# servo_controller.net
KiCad netlist of a schematic drawn in EAGLE
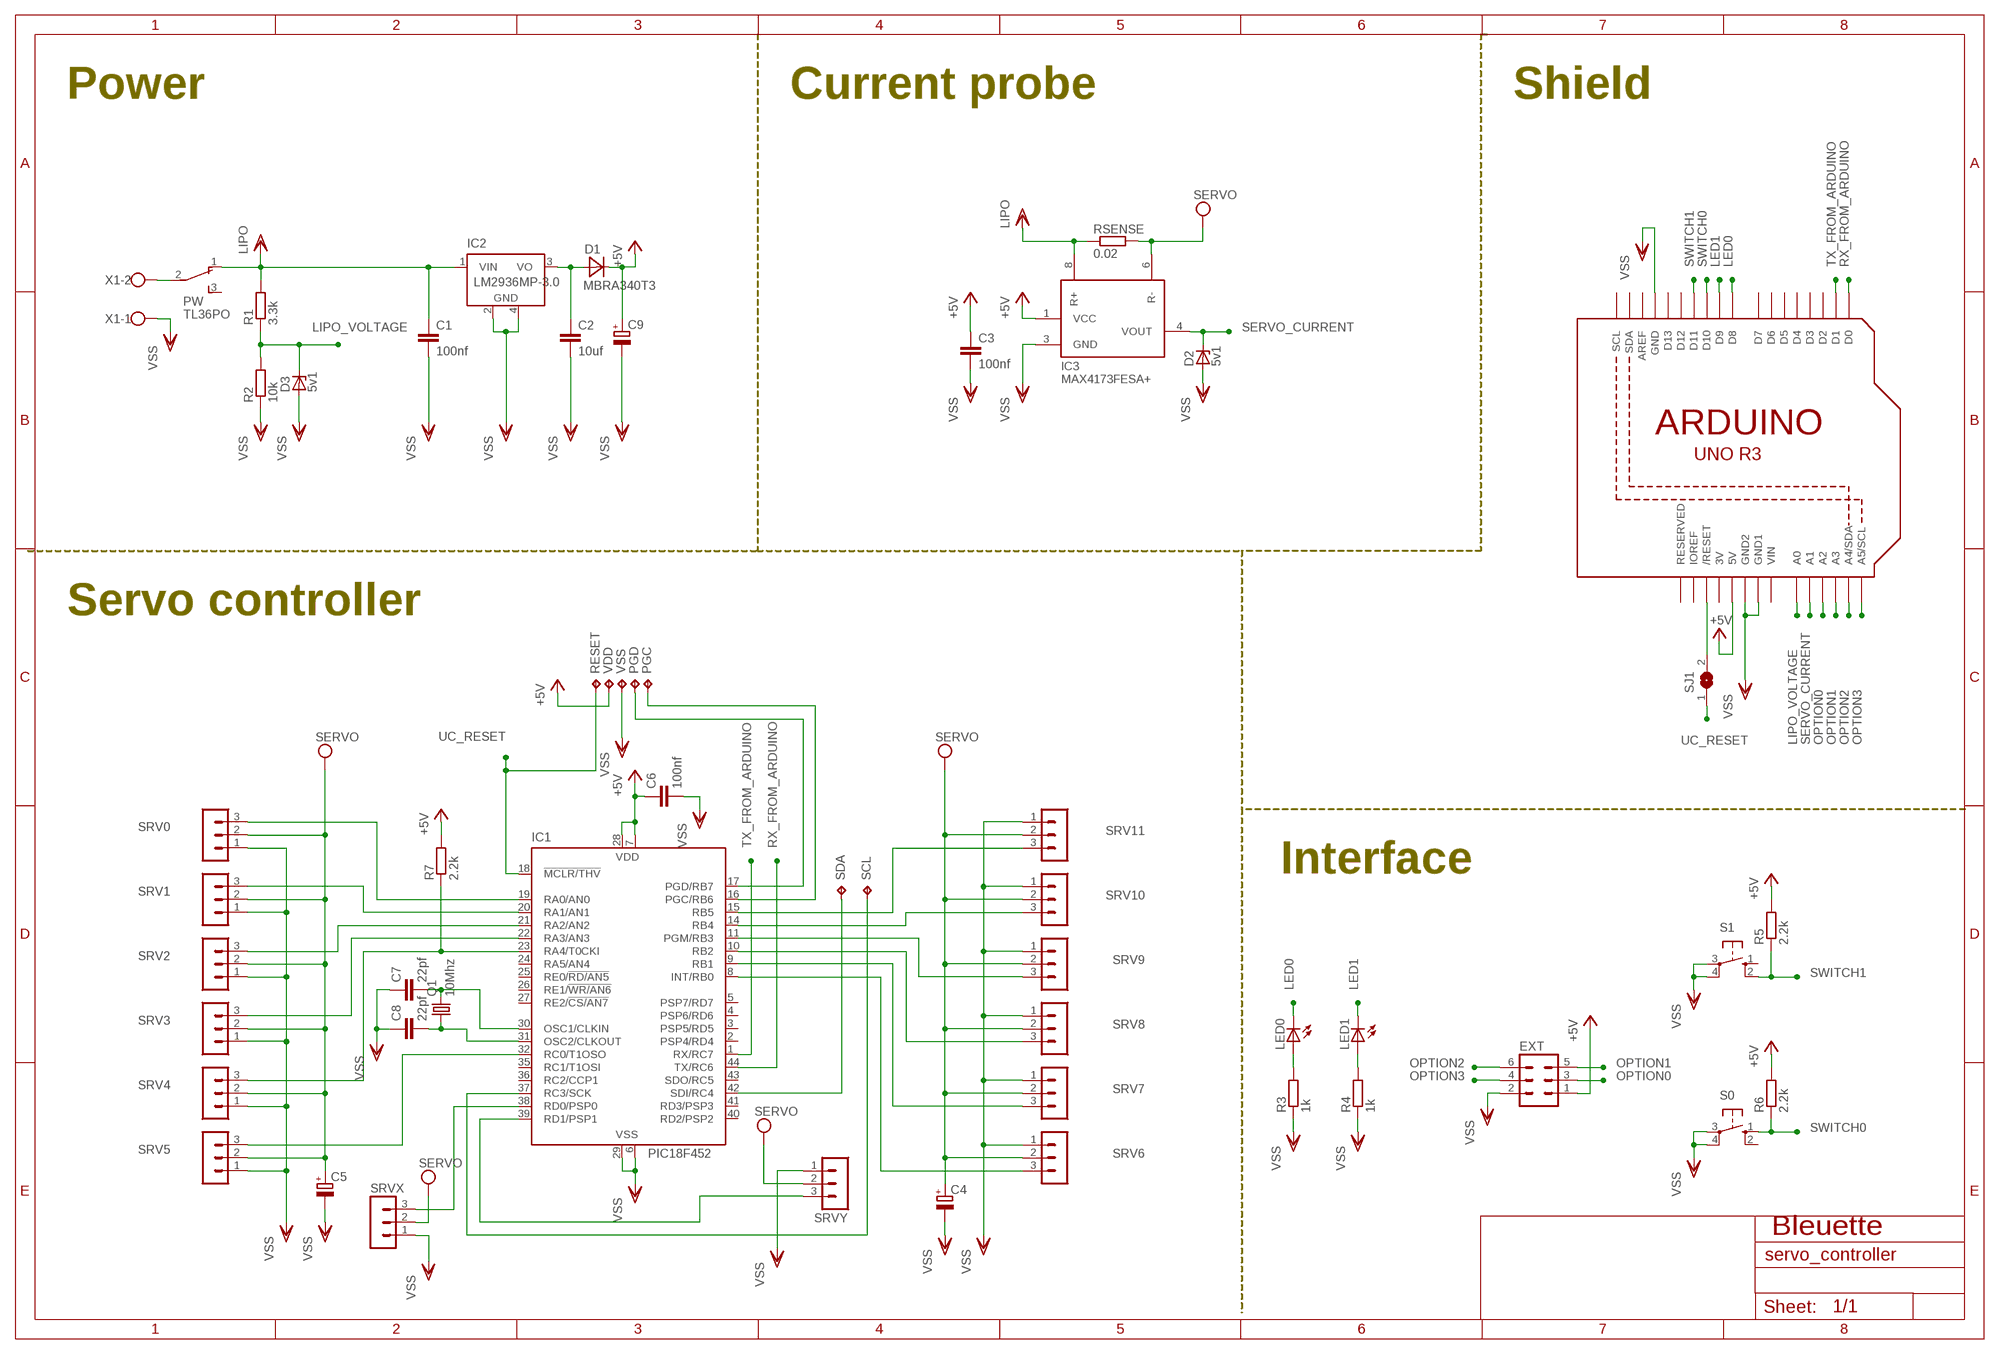
[diagram p0: schematic, sheet 1]

(export (version "E")
  (design (tool "Eeschema 10.0.6"))
  (components
    (comp (ref "C1")
      (value "100nf")
      (footprint "eagle-import:C1206")
      (libsource (lib "eagle-import") (part "C-EUC1206"))
    )
    (comp (ref "C2")
      (value "10uf")
      (footprint "eagle-import:C1206")
      (libsource (lib "eagle-import") (part "C-EUC1206"))
    )
    (comp (ref "C3")
      (value "100nf")
      (footprint "eagle-import:C1206")
      (libsource (lib "eagle-import") (part "C-EUC1206"))
    )
    (comp (ref "C4")
      (value "CPOL-EUD")
      (footprint "eagle-import:PANASONIC_D")
      (libsource (lib "eagle-import") (part "CPOL-EUD"))
    )
    (comp (ref "C5")
      (value "CPOL-EUD")
      (footprint "eagle-import:PANASONIC_D")
      (libsource (lib "eagle-import") (part "CPOL-EUD"))
    )
    (comp (ref "C6")
      (value "100nf")
      (footprint "eagle-import:C1206")
      (libsource (lib "eagle-import") (part "C-EUC1206"))
    )
    (comp (ref "C7")
      (value "22pf")
      (footprint "eagle-import:C1206")
      (libsource (lib "eagle-import") (part "C-EUC1206"))
    )
    (comp (ref "C8")
      (value "22pf")
      (footprint "eagle-import:C1206")
      (libsource (lib "eagle-import") (part "C-EUC1206"))
    )
    (comp (ref "C9")
      (value "CPOL-EUF")
      (footprint "eagle-import:PANASONIC_F")
      (libsource (lib "eagle-import") (part "CPOL-EUF"))
    )
    (comp (ref "D1")
      (value "MBRA340T3")
      (footprint "eagle-import:SMA")
      (libsource (lib "eagle-import") (part "MBRA340T3"))
    )
    (comp (ref "D2")
      (value "5v1")
      (footprint "eagle-import:SOT23")
      (libsource (lib "eagle-import") (part "ZENER-DIODESOT23"))
    )
    (comp (ref "D3")
      (value "5v1")
      (footprint "eagle-import:SOT23")
      (libsource (lib "eagle-import") (part "ZENER-DIODESOT23"))
    )
    (comp (ref "EXT")
      (value "MA03-2")
      (footprint "eagle-import:MA03-2")
      (libsource (lib "eagle-import") (part "MA03-2"))
    )
    (comp (ref "IC1")
      (value "PIC18F452")
      (footprint "eagle-import:TQFP44")
      (fields (field (name "MF") "MICROCHIP") (field (name "MPN") "PIC16F877-04/PQ"))
      (libsource (lib "eagle-import") (part "PIC16F87PT7"))
    )
    (comp (ref "IC2")
      (value "LM2936MP-3.0")
      (footprint "eagle-import:SOT223")
      (fields (field (name "MF") "NATIONAL SEMICONDUCTOR") (field (name "MPN") "LM2936MP-3.0/NOPB"))
      (libsource (lib "eagle-import") (part "LM2936MP?-3.0"))
    )
    (comp (ref "IC3")
      (value "MAX4173FESA+")
      (footprint "eagle-import:SO08")
      (libsource (lib "eagle-import") (part "MAX4173A"))
    )
    (comp (ref "LED0")
      (value "LEDCHIPLED_0805")
      (footprint "eagle-import:CHIPLED_0805")
      (libsource (lib "eagle-import") (part "LEDCHIPLED_0805"))
    )
    (comp (ref "LED1")
      (value "LEDCHIPLED_0805")
      (footprint "eagle-import:CHIPLED_0805")
      (libsource (lib "eagle-import") (part "LEDCHIPLED_0805"))
    )
    (comp (ref "PGC")
      (value "TPTP20R")
      (footprint "eagle-import:TP20R")
      (libsource (lib "eagle-import") (part "TPTP20R"))
    )
    (comp (ref "PGD")
      (value "TPTP20R")
      (footprint "eagle-import:TP20R")
      (libsource (lib "eagle-import") (part "TPTP20R"))
    )
    (comp (ref "PW")
      (value "TL36PO")
      (footprint "eagle-import:TL3XPO")
      (libsource (lib "eagle-import") (part "TL36PO"))
    )
    (comp (ref "Q1")
      (value "10Mhz")
      (footprint "eagle-import:HC49UP")
      (libsource (lib "eagle-import") (part "CRYTALHC49UP"))
    )
    (comp (ref "R1")
      (value "3.3k")
      (footprint "eagle-import:M1206")
      (libsource (lib "eagle-import") (part "R-EU_M1206"))
    )
    (comp (ref "R2")
      (value "10k")
      (footprint "eagle-import:M1206")
      (libsource (lib "eagle-import") (part "R-EU_M1206"))
    )
    (comp (ref "R3")
      (value "1k")
      (footprint "eagle-import:M0805")
      (libsource (lib "eagle-import") (part "R-EU_M0805"))
    )
    (comp (ref "R4")
      (value "1k")
      (footprint "eagle-import:M0805")
      (libsource (lib "eagle-import") (part "R-EU_M0805"))
    )
    (comp (ref "R5")
      (value "2.2k")
      (footprint "eagle-import:M0805")
      (libsource (lib "eagle-import") (part "R-EU_M0805"))
    )
    (comp (ref "R6")
      (value "2.2k")
      (footprint "eagle-import:M0805")
      (libsource (lib "eagle-import") (part "R-EU_M0805"))
    )
    (comp (ref "R7")
      (value "2.2k")
      (footprint "eagle-import:M0805")
      (libsource (lib "eagle-import") (part "R-EU_M0805"))
    )
    (comp (ref "RESET")
      (value "TPTP20R")
      (footprint "eagle-import:TP20R")
      (libsource (lib "eagle-import") (part "TPTP20R"))
    )
    (comp (ref "RSENSE")
      (value "0.02")
      (footprint "eagle-import:R4527")
      (libsource (lib "eagle-import") (part "R-EU_R4527"))
    )
    (comp (ref "S0")
      (value "10-XX")
      (footprint "eagle-import:B3F-10XX")
      (fields (field (name "MPN") "B3F-1000"))
      (libsource (lib "eagle-import") (part "10-XX"))
    )
    (comp (ref "S1")
      (value "10-XX")
      (footprint "eagle-import:B3F-10XX")
      (fields (field (name "MPN") "B3F-1000"))
      (libsource (lib "eagle-import") (part "10-XX"))
    )
    (comp (ref "SCL")
      (value "TPTP20R")
      (footprint "eagle-import:TP20R")
      (libsource (lib "eagle-import") (part "TPTP20R"))
    )
    (comp (ref "SDA")
      (value "TPTP20R")
      (footprint "eagle-import:TP20R")
      (libsource (lib "eagle-import") (part "TPTP20R"))
    )
    (comp (ref "SJ1") (value "SJ") (footprint "eagle-import:SJ") (libsource (lib "eagle-import") (part "SJ")))
    (comp (ref "SRV0")
      (value "MA03-1")
      (footprint "eagle-import:MA03-1")
      (libsource (lib "eagle-import") (part "MA03-1"))
    )
    (comp (ref "SRV1")
      (value "MA03-1")
      (footprint "eagle-import:MA03-1")
      (libsource (lib "eagle-import") (part "MA03-1"))
    )
    (comp (ref "SRV2")
      (value "MA03-1")
      (footprint "eagle-import:MA03-1")
      (libsource (lib "eagle-import") (part "MA03-1"))
    )
    (comp (ref "SRV3")
      (value "MA03-1")
      (footprint "eagle-import:MA03-1")
      (libsource (lib "eagle-import") (part "MA03-1"))
    )
    (comp (ref "SRV4")
      (value "MA03-1")
      (footprint "eagle-import:MA03-1")
      (libsource (lib "eagle-import") (part "MA03-1"))
    )
    (comp (ref "SRV5")
      (value "MA03-1")
      (footprint "eagle-import:MA03-1")
      (libsource (lib "eagle-import") (part "MA03-1"))
    )
    (comp (ref "SRV6")
      (value "MA03-1")
      (footprint "eagle-import:MA03-1")
      (libsource (lib "eagle-import") (part "MA03-1"))
    )
    (comp (ref "SRV7")
      (value "MA03-1")
      (footprint "eagle-import:MA03-1")
      (libsource (lib "eagle-import") (part "MA03-1"))
    )
    (comp (ref "SRV8")
      (value "MA03-1")
      (footprint "eagle-import:MA03-1")
      (libsource (lib "eagle-import") (part "MA03-1"))
    )
    (comp (ref "SRV9")
      (value "MA03-1")
      (footprint "eagle-import:MA03-1")
      (libsource (lib "eagle-import") (part "MA03-1"))
    )
    (comp (ref "SRV10")
      (value "MA03-1")
      (footprint "eagle-import:MA03-1")
      (libsource (lib "eagle-import") (part "MA03-1"))
    )
    (comp (ref "SRV11")
      (value "MA03-1")
      (footprint "eagle-import:MA03-1")
      (libsource (lib "eagle-import") (part "MA03-1"))
    )
    (comp (ref "SRVX")
      (value "MA03-1")
      (footprint "eagle-import:MA03-1")
      (libsource (lib "eagle-import") (part "MA03-1"))
    )
    (comp (ref "SRVY")
      (value "MA03-1")
      (footprint "eagle-import:MA03-1")
      (libsource (lib "eagle-import") (part "MA03-1"))
    )
    (comp (ref "U1")
      (value "ARDUINOR3-DIMENSION")
      (footprint "eagle-import:ARDUINOR3")
      (libsource (lib "eagle-import") (part "ARDUINOR3-DIMENSION"))
    )
    (comp (ref "VDD")
      (value "TPTP20R")
      (footprint "eagle-import:TP20R")
      (libsource (lib "eagle-import") (part "TPTP20R"))
    )
    (comp (ref "VSS")
      (value "TPTP20R")
      (footprint "eagle-import:TP20R")
      (libsource (lib "eagle-import") (part "TPTP20R"))
    )
    (comp (ref "X1")
      (value "W237-102")
      (footprint "eagle-import:W237-102")
      (fields (field (name "MPN") "237-102"))
      (libsource (lib "eagle-import") (part "W237-102"))
    )
  )
  (nets
    (net (code "1") (name "+5V") (class "Default")
      (node (ref "C3") (pin "1") (pinfunction "1_1") (pintype "passive"))
      (node (ref "C6") (pin "1") (pinfunction "1_1") (pintype "passive"))
      (node (ref "C9") (pin "+") (pinfunction "+_+") (pintype "passive"))
      (node (ref "D1") (pin "C") (pinfunction "C_C") (pintype "passive"))
      (node (ref "EXT") (pin "1") (pinfunction "1_1") (pintype "passive"))
      (node (ref "IC1") (pin "28") (pinfunction "VDD_28") (pintype "power_in"))
      (node (ref "IC1") (pin "7") (pinfunction "VDD_7") (pintype "power_in"))
      (node (ref "IC3") (pin "1") (pinfunction "VCC_1") (pintype "power_in"))
      (node (ref "R5") (pin "2") (pinfunction "2_2") (pintype "passive"))
      (node (ref "R6") (pin "2") (pinfunction "2_2") (pintype "passive"))
      (node (ref "R7") (pin "2") (pinfunction "2_2") (pintype "passive"))
      (node (ref "U1") (pin "5V") (pinfunction "5V_5V") (pintype "power_in"))
      (node (ref "VDD") (pin "TP") (pinfunction "TP_TP") (pintype "input"))
    )
    (net (code "2") (name "/3V") (class "Default")
      (node (ref "U1") (pin "3V") (pinfunction "3V_3V") (pintype "power_in"))
    )
    (net (code "3") (name "/LED0") (class "Default")
      (node (ref "LED0") (pin "C") (pinfunction "C_C") (pintype "passive"))
      (node (ref "U1") (pin "D8") (pinfunction "D8_D8") (pintype "bidirectional"))
    )
    (net (code "4") (name "/LED1") (class "Default")
      (node (ref "LED1") (pin "C") (pinfunction "C_C") (pintype "passive"))
      (node (ref "U1") (pin "D9") (pinfunction "D9_D9") (pintype "bidirectional"))
    )
    (net (code "5") (name "/LIPO_VOLTAGE") (class "Default")
      (node (ref "D3") (pin "3") (pinfunction "C_3") (pintype "passive"))
      (node (ref "R1") (pin "1") (pinfunction "1_1") (pintype "passive"))
      (node (ref "R2") (pin "2") (pinfunction "2_2") (pintype "passive"))
      (node (ref "U1") (pin "A0") (pinfunction "A0_A0") (pintype "bidirectional"))
    )
    (net (code "6") (name "/OPTION0") (class "Default")
      (node (ref "EXT") (pin "3") (pinfunction "3_3") (pintype "passive"))
      (node (ref "U1") (pin "A2") (pinfunction "A2_A2") (pintype "bidirectional"))
    )
    (net (code "7") (name "/OPTION1") (class "Default")
      (node (ref "EXT") (pin "5") (pinfunction "5_5") (pintype "passive"))
      (node (ref "U1") (pin "A3") (pinfunction "A3_A3") (pintype "bidirectional"))
    )
    (net (code "8") (name "/OPTION2") (class "Default")
      (node (ref "EXT") (pin "6") (pinfunction "6_6") (pintype "passive"))
      (node (ref "U1") (pin "A4") (pinfunction "A4/SDA_A4") (pintype "bidirectional"))
    )
    (net (code "9") (name "/OPTION3") (class "Default")
      (node (ref "EXT") (pin "4") (pinfunction "4_4") (pintype "passive"))
      (node (ref "U1") (pin "A5") (pinfunction "A5/SCL_A5") (pintype "bidirectional"))
    )
    (net (code "10") (name "/RX_FROM_ARDUINO") (class "Default")
      (node (ref "IC1") (pin "44") (pinfunction "TX/RC6_44") (pintype "bidirectional"))
      (node (ref "U1") (pin "D0") (pinfunction "D0_D0") (pintype "bidirectional"))
    )
    (net (code "11") (name "/SERVO_CURRENT") (class "Default")
      (node (ref "D2") (pin "3") (pinfunction "C_3") (pintype "passive"))
      (node (ref "IC3") (pin "4") (pinfunction "VOUT_4") (pintype "output"))
      (node (ref "U1") (pin "A1") (pinfunction "A1_A1") (pintype "bidirectional"))
    )
    (net (code "12") (name "/SWITCH0") (class "Default")
      (node (ref "R6") (pin "1") (pinfunction "1_1") (pintype "passive"))
      (node (ref "S0") (pin "1") (pinfunction "S_1") (pintype "passive"))
      (node (ref "U1") (pin "D10") (pinfunction "D10_D10") (pintype "bidirectional"))
    )
    (net (code "13") (name "/SWITCH1") (class "Default")
      (node (ref "R5") (pin "1") (pinfunction "1_1") (pintype "passive"))
      (node (ref "S1") (pin "2") (pinfunction "S1_2") (pintype "passive"))
      (node (ref "U1") (pin "D11") (pinfunction "D11_D11") (pintype "bidirectional"))
    )
    (net (code "14") (name "/TX_FROM_ARDUINO") (class "Default")
      (node (ref "IC1") (pin "1") (pinfunction "RX/RC7_1") (pintype "bidirectional"))
      (node (ref "U1") (pin "D1") (pinfunction "D1_D1") (pintype "bidirectional"))
    )
    (net (code "15") (name "/UC_RESET") (class "Default")
      (node (ref "IC1") (pin "18") (pinfunction "~{MCLR/THV}_18") (pintype "input"))
      (node (ref "RESET") (pin "TP") (pinfunction "TP_TP") (pintype "input"))
      (node (ref "SJ1") (pin "1") (pinfunction "1_1") (pintype "passive"))
    )
    (net (code "16") (name "/VIN") (class "Default")
      (node (ref "U1") (pin "VIN") (pinfunction "VIN_VIN") (pintype "power_in"))
    )
    (net (code "17") (name "LIPO") (class "Default")
      (node (ref "C1") (pin "1") (pinfunction "1_1") (pintype "passive"))
      (node (ref "IC2") (pin "1") (pinfunction "VIN_1") (pintype "input"))
      (node (ref "IC3") (pin "8") (pinfunction "R+_8") (pintype "input"))
      (node (ref "PW") (pin "1") (pinfunction "O_1") (pintype "passive"))
      (node (ref "R1") (pin "2") (pinfunction "2_2") (pintype "passive"))
      (node (ref "RSENSE") (pin "1") (pinfunction "1_1") (pintype "passive"))
    )
    (net (code "18") (name "Net-(IC1-INT{slash}RB0)") (class "Default")
      (node (ref "IC1") (pin "8") (pinfunction "INT/RB0_8") (pintype "bidirectional"))
      (node (ref "SRV6") (pin "3") (pinfunction "3_3") (pintype "passive"))
    )
    (net (code "19") (name "Net-(IC1-OSC1{slash}CLKIN)") (class "Default")
      (node (ref "C7") (pin "2") (pinfunction "2_2") (pintype "passive"))
      (node (ref "IC1") (pin "30") (pinfunction "OSC1/CLKIN_30") (pintype "input"))
      (node (ref "Q1") (pin "2") (pinfunction "2_2") (pintype "passive"))
    )
    (net (code "20") (name "Net-(IC1-OSC2{slash}CLKOUT)") (class "Default")
      (node (ref "C8") (pin "2") (pinfunction "2_2") (pintype "passive"))
      (node (ref "IC1") (pin "31") (pinfunction "OSC2/CLKOUT_31") (pintype "output"))
      (node (ref "Q1") (pin "1") (pinfunction "1_1") (pintype "passive"))
    )
    (net (code "21") (name "Net-(IC1-PGC{slash}RB6)") (class "Default")
      (node (ref "IC1") (pin "16") (pinfunction "PGC/RB6_16") (pintype "bidirectional"))
      (node (ref "PGC") (pin "TP") (pinfunction "TP_TP") (pintype "input"))
    )
    (net (code "22") (name "Net-(IC1-PGD{slash}RB7)") (class "Default")
      (node (ref "IC1") (pin "17") (pinfunction "PGD/RB7_17") (pintype "bidirectional"))
      (node (ref "PGD") (pin "TP") (pinfunction "TP_TP") (pintype "input"))
    )
    (net (code "23") (name "Net-(IC1-PGM{slash}RB3)") (class "Default")
      (node (ref "IC1") (pin "11") (pinfunction "PGM/RB3_11") (pintype "bidirectional"))
      (node (ref "SRV9") (pin "3") (pinfunction "3_3") (pintype "passive"))
    )
    (net (code "24") (name "Net-(IC1-RA0{slash}AN0)") (class "Default")
      (node (ref "IC1") (pin "19") (pinfunction "RA0/AN0_19") (pintype "bidirectional"))
      (node (ref "SRV0") (pin "3") (pinfunction "3_3") (pintype "passive"))
    )
    (net (code "25") (name "Net-(IC1-RA1{slash}AN1)") (class "Default")
      (node (ref "IC1") (pin "20") (pinfunction "RA1/AN1_20") (pintype "bidirectional"))
      (node (ref "SRV1") (pin "3") (pinfunction "3_3") (pintype "passive"))
    )
    (net (code "26") (name "Net-(IC1-RA2{slash}AN2)") (class "Default")
      (node (ref "IC1") (pin "21") (pinfunction "RA2/AN2_21") (pintype "bidirectional"))
      (node (ref "SRV2") (pin "3") (pinfunction "3_3") (pintype "passive"))
    )
    (net (code "27") (name "Net-(IC1-RA3{slash}AN3)") (class "Default")
      (node (ref "IC1") (pin "22") (pinfunction "RA3/AN3_22") (pintype "bidirectional"))
      (node (ref "SRV3") (pin "3") (pinfunction "3_3") (pintype "passive"))
    )
    (net (code "28") (name "Net-(IC1-RA4{slash}T0CKI)") (class "Default")
      (node (ref "IC1") (pin "23") (pinfunction "RA4/T0CKI_23") (pintype "bidirectional"))
      (node (ref "R7") (pin "1") (pinfunction "1_1") (pintype "passive"))
      (node (ref "SRV4") (pin "3") (pinfunction "3_3") (pintype "passive"))
    )
    (net (code "29") (name "Net-(IC1-RB1)") (class "Default")
      (node (ref "IC1") (pin "9") (pinfunction "RB1_9") (pintype "bidirectional"))
      (node (ref "SRV7") (pin "3") (pinfunction "3_3") (pintype "passive"))
    )
    (net (code "30") (name "Net-(IC1-RB2)") (class "Default")
      (node (ref "IC1") (pin "10") (pinfunction "RB2_10") (pintype "bidirectional"))
      (node (ref "SRV8") (pin "3") (pinfunction "3_3") (pintype "passive"))
    )
    (net (code "31") (name "Net-(IC1-RB4)") (class "Default")
      (node (ref "IC1") (pin "14") (pinfunction "RB4_14") (pintype "bidirectional"))
      (node (ref "SRV10") (pin "3") (pinfunction "3_3") (pintype "passive"))
    )
    (net (code "32") (name "Net-(IC1-RB5)") (class "Default")
      (node (ref "IC1") (pin "15") (pinfunction "RB5_15") (pintype "bidirectional"))
      (node (ref "SRV11") (pin "3") (pinfunction "3_3") (pintype "passive"))
    )
    (net (code "33") (name "Net-(IC1-RC0{slash}T1OSO)") (class "Default")
      (node (ref "IC1") (pin "32") (pinfunction "RC0/T1OSO_32") (pintype "bidirectional"))
      (node (ref "SRV5") (pin "3") (pinfunction "3_3") (pintype "passive"))
    )
    (net (code "34") (name "Net-(IC1-RC3{slash}SCK)") (class "Default")
      (node (ref "IC1") (pin "37") (pinfunction "RC3/SCK_37") (pintype "bidirectional"))
      (node (ref "SCL") (pin "TP") (pinfunction "TP_TP") (pintype "input"))
    )
    (net (code "35") (name "Net-(IC1-RD0{slash}PSP0)") (class "Default")
      (node (ref "IC1") (pin "38") (pinfunction "RD0/PSP0_38") (pintype "bidirectional"))
      (node (ref "SRVX") (pin "3") (pinfunction "3_3") (pintype "passive"))
    )
    (net (code "36") (name "Net-(IC1-RD1{slash}PSP1)") (class "Default")
      (node (ref "IC1") (pin "39") (pinfunction "RD1/PSP1_39") (pintype "bidirectional"))
      (node (ref "SRVY") (pin "3") (pinfunction "3_3") (pintype "passive"))
    )
    (net (code "37") (name "Net-(IC1-SDI{slash}RC4)") (class "Default")
      (node (ref "IC1") (pin "42") (pinfunction "SDI/RC4_42") (pintype "bidirectional"))
      (node (ref "SDA") (pin "TP") (pinfunction "TP_TP") (pintype "input"))
    )
    (net (code "38") (name "Net-(IC2-VO)") (class "Default")
      (node (ref "C2") (pin "1") (pinfunction "1_1") (pintype "passive"))
      (node (ref "D1") (pin "A") (pinfunction "A_A") (pintype "passive"))
      (node (ref "IC2") (pin "3") (pinfunction "VO_3") (pintype "passive"))
    )
    (net (code "39") (name "Net-(LED0-PadA)") (class "Default")
      (node (ref "LED0") (pin "A") (pinfunction "A_A") (pintype "passive"))
      (node (ref "R3") (pin "2") (pinfunction "2_2") (pintype "passive"))
    )
    (net (code "40") (name "Net-(LED1-PadA)") (class "Default")
      (node (ref "LED1") (pin "A") (pinfunction "A_A") (pintype "passive"))
      (node (ref "R4") (pin "2") (pinfunction "2_2") (pintype "passive"))
    )
    (net (code "41") (name "Net-(PW-P)") (class "Default")
      (node (ref "PW") (pin "2") (pinfunction "P_2") (pintype "passive"))
      (node (ref "X1") (pin "2") (pinfunction "KL_2") (pintype "passive"))
    )
    (net (code "42") (name "Net-(U1-{slash}RESET)") (class "Default")
      (node (ref "SJ1") (pin "2") (pinfunction "2_2") (pintype "passive"))
      (node (ref "U1") (pin "RESET") (pinfunction "/RESET_RESET") (pintype "bidirectional"))
    )
    (net (code "43") (name "SERVO") (class "Default")
      (node (ref "C4") (pin "+") (pinfunction "+_+") (pintype "passive"))
      (node (ref "C5") (pin "+") (pinfunction "+_+") (pintype "passive"))
      (node (ref "IC3") (pin "6") (pinfunction "R-_6") (pintype "input"))
      (node (ref "RSENSE") (pin "2") (pinfunction "2_2") (pintype "passive"))
      (node (ref "SRV0") (pin "2") (pinfunction "2_2") (pintype "passive"))
      (node (ref "SRV1") (pin "2") (pinfunction "2_2") (pintype "passive"))
      (node (ref "SRV10") (pin "2") (pinfunction "2_2") (pintype "passive"))
      (node (ref "SRV11") (pin "2") (pinfunction "2_2") (pintype "passive"))
      (node (ref "SRV2") (pin "2") (pinfunction "2_2") (pintype "passive"))
      (node (ref "SRV3") (pin "2") (pinfunction "2_2") (pintype "passive"))
      (node (ref "SRV4") (pin "2") (pinfunction "2_2") (pintype "passive"))
      (node (ref "SRV5") (pin "2") (pinfunction "2_2") (pintype "passive"))
      (node (ref "SRV6") (pin "2") (pinfunction "2_2") (pintype "passive"))
      (node (ref "SRV7") (pin "2") (pinfunction "2_2") (pintype "passive"))
      (node (ref "SRV8") (pin "2") (pinfunction "2_2") (pintype "passive"))
      (node (ref "SRV9") (pin "2") (pinfunction "2_2") (pintype "passive"))
      (node (ref "SRVX") (pin "2") (pinfunction "2_2") (pintype "passive"))
      (node (ref "SRVY") (pin "2") (pinfunction "2_2") (pintype "passive"))
    )
    (net (code "44") (name "VSS") (class "Default")
      (node (ref "C1") (pin "2") (pinfunction "2_2") (pintype "passive"))
      (node (ref "C2") (pin "2") (pinfunction "2_2") (pintype "passive"))
      (node (ref "C3") (pin "2") (pinfunction "2_2") (pintype "passive"))
      (node (ref "C4") (pin "-") (pinfunction "-_-") (pintype "passive"))
      (node (ref "C5") (pin "-") (pinfunction "-_-") (pintype "passive"))
      (node (ref "C6") (pin "2") (pinfunction "2_2") (pintype "passive"))
      (node (ref "C7") (pin "1") (pinfunction "1_1") (pintype "passive"))
      (node (ref "C8") (pin "1") (pinfunction "1_1") (pintype "passive"))
      (node (ref "C9") (pin "-") (pinfunction "-_-") (pintype "passive"))
      (node (ref "D2") (pin "1") (pinfunction "A_1") (pintype "passive"))
      (node (ref "D3") (pin "1") (pinfunction "A_1") (pintype "passive"))
      (node (ref "EXT") (pin "2") (pinfunction "2_2") (pintype "passive"))
      (node (ref "IC1") (pin "29") (pinfunction "VSS_29") (pintype "power_in"))
      (node (ref "IC1") (pin "6") (pinfunction "VSS_6") (pintype "power_in"))
      (node (ref "IC2") (pin "2") (pinfunction "GND_2") (pintype "passive"))
      (node (ref "IC2") (pin "4") (pinfunction "GND_4") (pintype "passive"))
      (node (ref "IC3") (pin "3") (pinfunction "GND_3") (pintype "power_in"))
      (node (ref "R2") (pin "1") (pinfunction "1_1") (pintype "passive"))
      (node (ref "R3") (pin "1") (pinfunction "1_1") (pintype "passive"))
      (node (ref "R4") (pin "1") (pinfunction "1_1") (pintype "passive"))
      (node (ref "S0") (pin "3") (pinfunction "P_3") (pintype "passive"))
      (node (ref "S0") (pin "4") (pinfunction "P1_4") (pintype "passive"))
      (node (ref "S1") (pin "3") (pinfunction "P_3") (pintype "passive"))
      (node (ref "S1") (pin "4") (pinfunction "P1_4") (pintype "passive"))
      (node (ref "SRV0") (pin "1") (pinfunction "1_1") (pintype "passive"))
      (node (ref "SRV1") (pin "1") (pinfunction "1_1") (pintype "passive"))
      (node (ref "SRV10") (pin "1") (pinfunction "1_1") (pintype "passive"))
      (node (ref "SRV11") (pin "1") (pinfunction "1_1") (pintype "passive"))
      (node (ref "SRV2") (pin "1") (pinfunction "1_1") (pintype "passive"))
      (node (ref "SRV3") (pin "1") (pinfunction "1_1") (pintype "passive"))
      (node (ref "SRV4") (pin "1") (pinfunction "1_1") (pintype "passive"))
      (node (ref "SRV5") (pin "1") (pinfunction "1_1") (pintype "passive"))
      (node (ref "SRV6") (pin "1") (pinfunction "1_1") (pintype "passive"))
      (node (ref "SRV7") (pin "1") (pinfunction "1_1") (pintype "passive"))
      (node (ref "SRV8") (pin "1") (pinfunction "1_1") (pintype "passive"))
      (node (ref "SRV9") (pin "1") (pinfunction "1_1") (pintype "passive"))
      (node (ref "SRVX") (pin "1") (pinfunction "1_1") (pintype "passive"))
      (node (ref "SRVY") (pin "1") (pinfunction "1_1") (pintype "passive"))
      (node (ref "U1") (pin "GND") (pinfunction "GND_GND") (pintype "power_in"))
      (node (ref "U1") (pin "GND1") (pinfunction "GND1_GND1") (pintype "power_in"))
      (node (ref "U1") (pin "GND2") (pinfunction "GND2_GND2") (pintype "power_in"))
      (node (ref "VSS") (pin "TP") (pinfunction "TP_TP") (pintype "input"))
      (node (ref "X1") (pin "1") (pinfunction "KL_1") (pintype "passive"))
    )
    (net (code "45") (name "unconnected-(IC1-PSP4{slash}RD4-Pad2)") (class "Default")
      (node (ref "IC1") (pin "2") (pinfunction "PSP4/RD4_2") (pintype "bidirectional"))
    )
    (net (code "46") (name "unconnected-(IC1-PSP5{slash}RD5-Pad3)") (class "Default")
      (node (ref "IC1") (pin "3") (pinfunction "PSP5/RD5_3") (pintype "bidirectional"))
    )
    (net (code "47") (name "unconnected-(IC1-PSP6{slash}RD6-Pad4)") (class "Default")
      (node (ref "IC1") (pin "4") (pinfunction "PSP6/RD6_4") (pintype "bidirectional"))
    )
    (net (code "48") (name "unconnected-(IC1-PSP7{slash}RD7-Pad5)") (class "Default")
      (node (ref "IC1") (pin "5") (pinfunction "PSP7/RD7_5") (pintype "bidirectional"))
    )
    (net (code "49") (name "unconnected-(IC1-RA5{slash}AN4-Pad24)") (class "Default")
      (node (ref "IC1") (pin "24") (pinfunction "RA5/AN4_24") (pintype "bidirectional"))
    )
    (net (code "50") (name "unconnected-(IC1-RC1{slash}T1OSI-Pad35)") (class "Default")
      (node (ref "IC1") (pin "35") (pinfunction "RC1/T1OSI_35") (pintype "bidirectional"))
    )
    (net (code "51") (name "unconnected-(IC1-RC2{slash}CCP1-Pad36)") (class "Default")
      (node (ref "IC1") (pin "36") (pinfunction "RC2/CCP1_36") (pintype "bidirectional"))
    )
    (net (code "52") (name "unconnected-(IC1-RD2{slash}PSP2-Pad40)") (class "Default")
      (node (ref "IC1") (pin "40") (pinfunction "RD2/PSP2_40") (pintype "bidirectional"))
    )
    (net (code "53") (name "unconnected-(IC1-RD3{slash}PSP3-Pad41)") (class "Default")
      (node (ref "IC1") (pin "41") (pinfunction "RD3/PSP3_41") (pintype "bidirectional"))
    )
    (net (code "54") (name "unconnected-(IC1-RE0{slash}~{RD{slash}AN5}-Pad25)") (class "Default")
      (node (ref "IC1") (pin "25") (pinfunction "RE0/~{RD/AN5}_25") (pintype "bidirectional"))
    )
    (net (code "55") (name "unconnected-(IC1-RE1{slash}~{WR{slash}AN6}-Pad26)") (class "Default")
      (node (ref "IC1") (pin "26") (pinfunction "RE1/~{WR/AN6}_26") (pintype "bidirectional"))
    )
    (net (code "56") (name "unconnected-(IC1-RE2{slash}~{CS{slash}AN7}-Pad27)") (class "Default")
      (node (ref "IC1") (pin "27") (pinfunction "RE2/~{CS/AN7}_27") (pintype "bidirectional"))
    )
    (net (code "57") (name "unconnected-(IC1-SDO{slash}RC5-Pad43)") (class "Default")
      (node (ref "IC1") (pin "43") (pinfunction "SDO/RC5_43") (pintype "bidirectional"))
    )
    (net (code "58") (name "unconnected-(PW-S-Pad3)") (class "Default")
      (node (ref "PW") (pin "3") (pinfunction "S_3") (pintype "passive"))
    )
    (net (code "59") (name "unconnected-(S0-S1-Pad2)") (class "Default")
      (node (ref "S0") (pin "2") (pinfunction "S1_2") (pintype "passive"))
    )
    (net (code "60") (name "unconnected-(S1-S-Pad1)") (class "Default")
      (node (ref "S1") (pin "1") (pinfunction "S_1") (pintype "passive"))
    )
    (net (code "61") (name "unconnected-(U1-PadAREF)") (class "Default")
      (node (ref "U1") (pin "AREF") (pinfunction "AREF_AREF") (pintype "bidirectional"))
    )
    (net (code "62") (name "unconnected-(U1-PadD2)") (class "Default")
      (node (ref "U1") (pin "D2") (pinfunction "D2_D2") (pintype "bidirectional"))
    )
    (net (code "63") (name "unconnected-(U1-PadD3)") (class "Default")
      (node (ref "U1") (pin "D3") (pinfunction "D3_D3") (pintype "bidirectional"))
    )
    (net (code "64") (name "unconnected-(U1-PadD4)") (class "Default")
      (node (ref "U1") (pin "D4") (pinfunction "D4_D4") (pintype "bidirectional"))
    )
    (net (code "65") (name "unconnected-(U1-PadD5)") (class "Default")
      (node (ref "U1") (pin "D5") (pinfunction "D5_D5") (pintype "bidirectional"))
    )
    (net (code "66") (name "unconnected-(U1-PadD6)") (class "Default")
      (node (ref "U1") (pin "D6") (pinfunction "D6_D6") (pintype "bidirectional"))
    )
    (net (code "67") (name "unconnected-(U1-PadD7)") (class "Default")
      (node (ref "U1") (pin "D7") (pinfunction "D7_D7") (pintype "bidirectional"))
    )
    (net (code "68") (name "unconnected-(U1-PadD12)") (class "Default")
      (node (ref "U1") (pin "D12") (pinfunction "D12_D12") (pintype "bidirectional"))
    )
    (net (code "69") (name "unconnected-(U1-PadD13)") (class "Default")
      (node (ref "U1") (pin "D13") (pinfunction "D13_D13") (pintype "bidirectional"))
    )
    (net (code "70") (name "unconnected-(U1-PadIOREF)") (class "Default")
      (node (ref "U1") (pin "IOREF") (pinfunction "IOREF_IOREF") (pintype "output"))
    )
    (net (code "71") (name "unconnected-(U1-PadRESERVED)") (class "Default")
      (node (ref "U1") (pin "RESERVED") (pinfunction "RESERVED_RESERVED") (pintype "no_connect"))
    )
    (net (code "72") (name "unconnected-(U1-PadSCL)") (class "Default")
      (node (ref "U1") (pin "SCL") (pinfunction "SCL_SCL") (pintype "bidirectional"))
    )
    (net (code "73") (name "unconnected-(U1-PadSDA)") (class "Default")
      (node (ref "U1") (pin "SDA") (pinfunction "SDA_SDA") (pintype "bidirectional"))
    )
  )
)
